# Macropad_schem_1.net
KiCad netlist of a schematic drawn in EAGLE
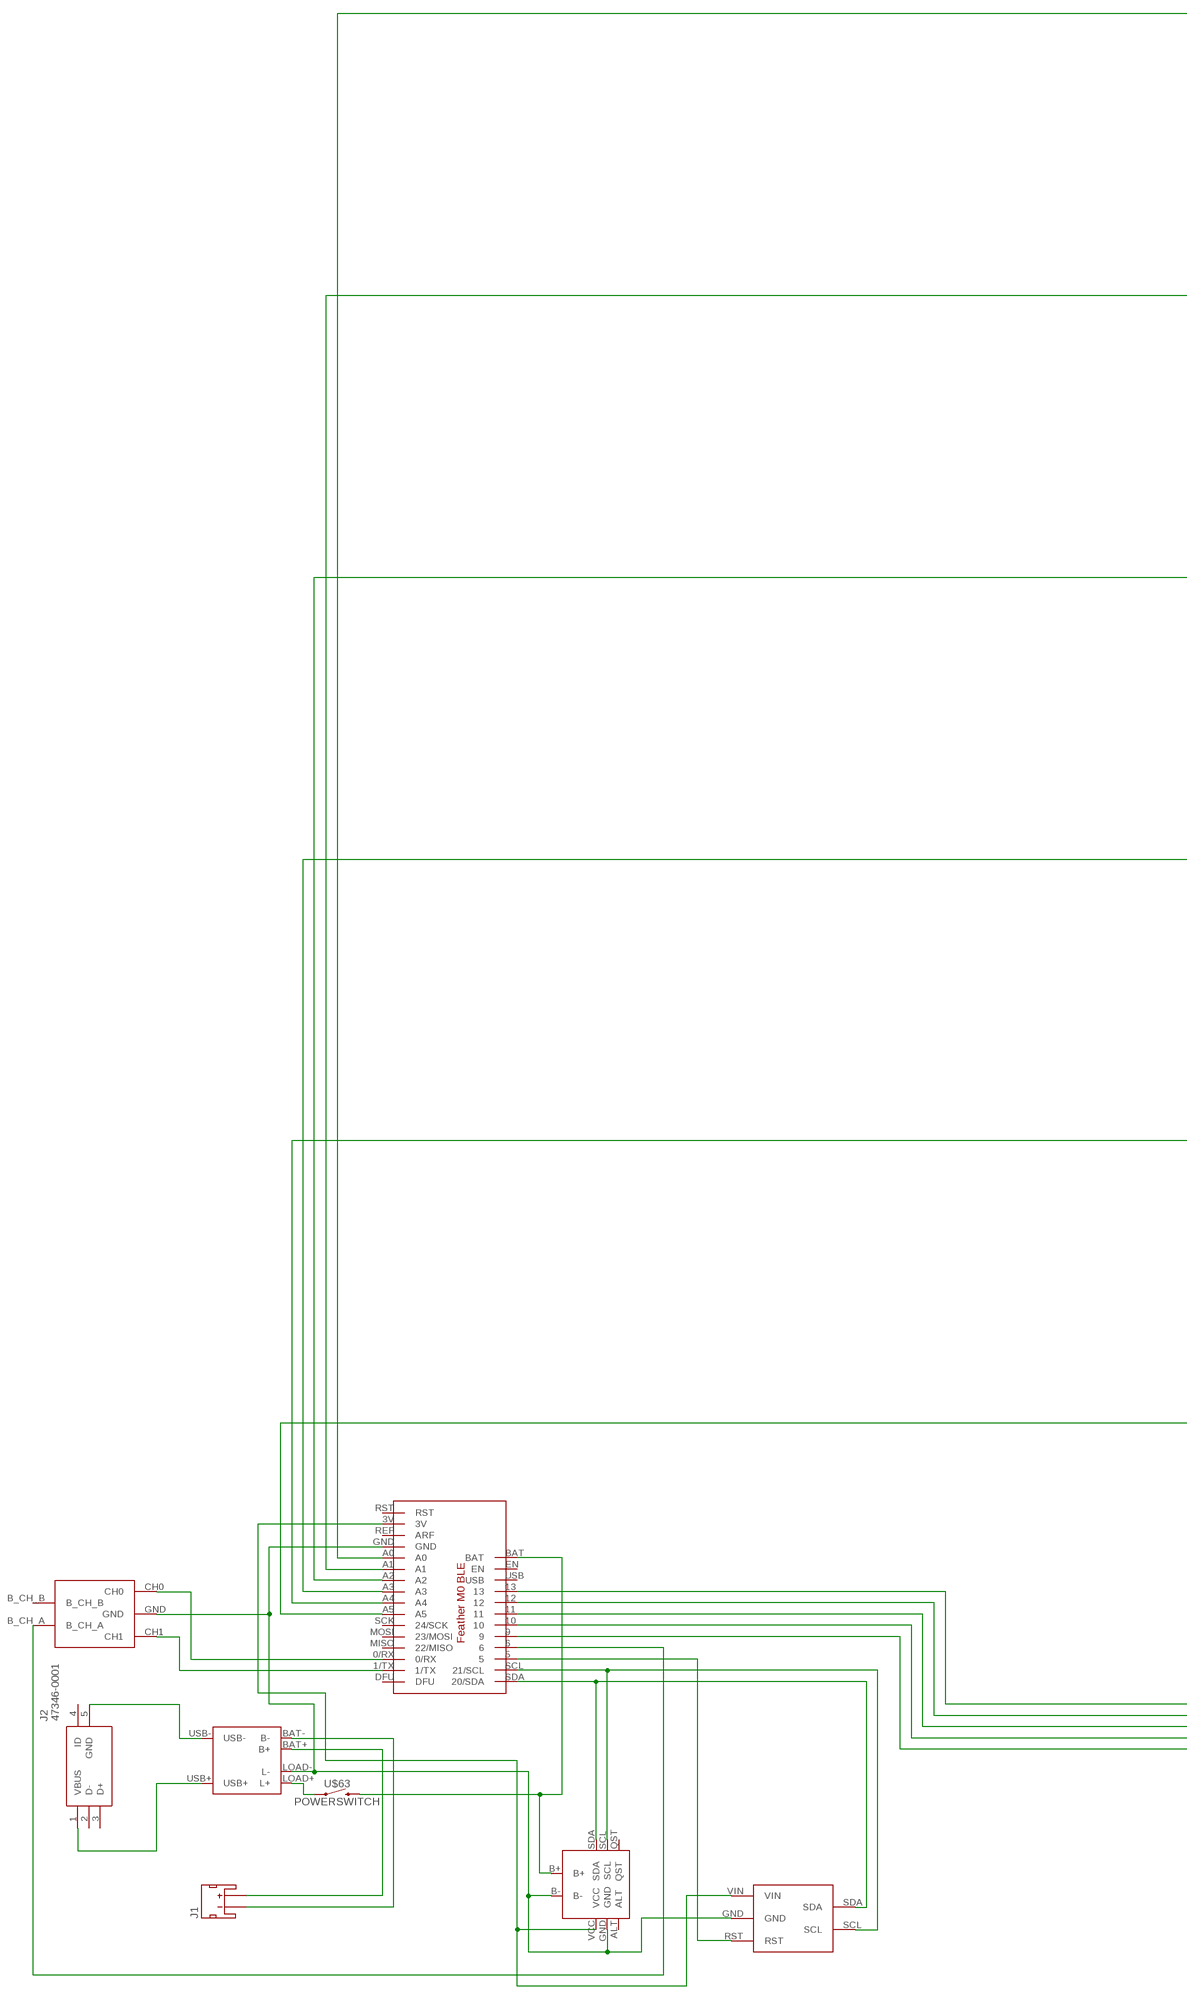
[diagram p0: schematic, sheet 1, part 1 of 2]
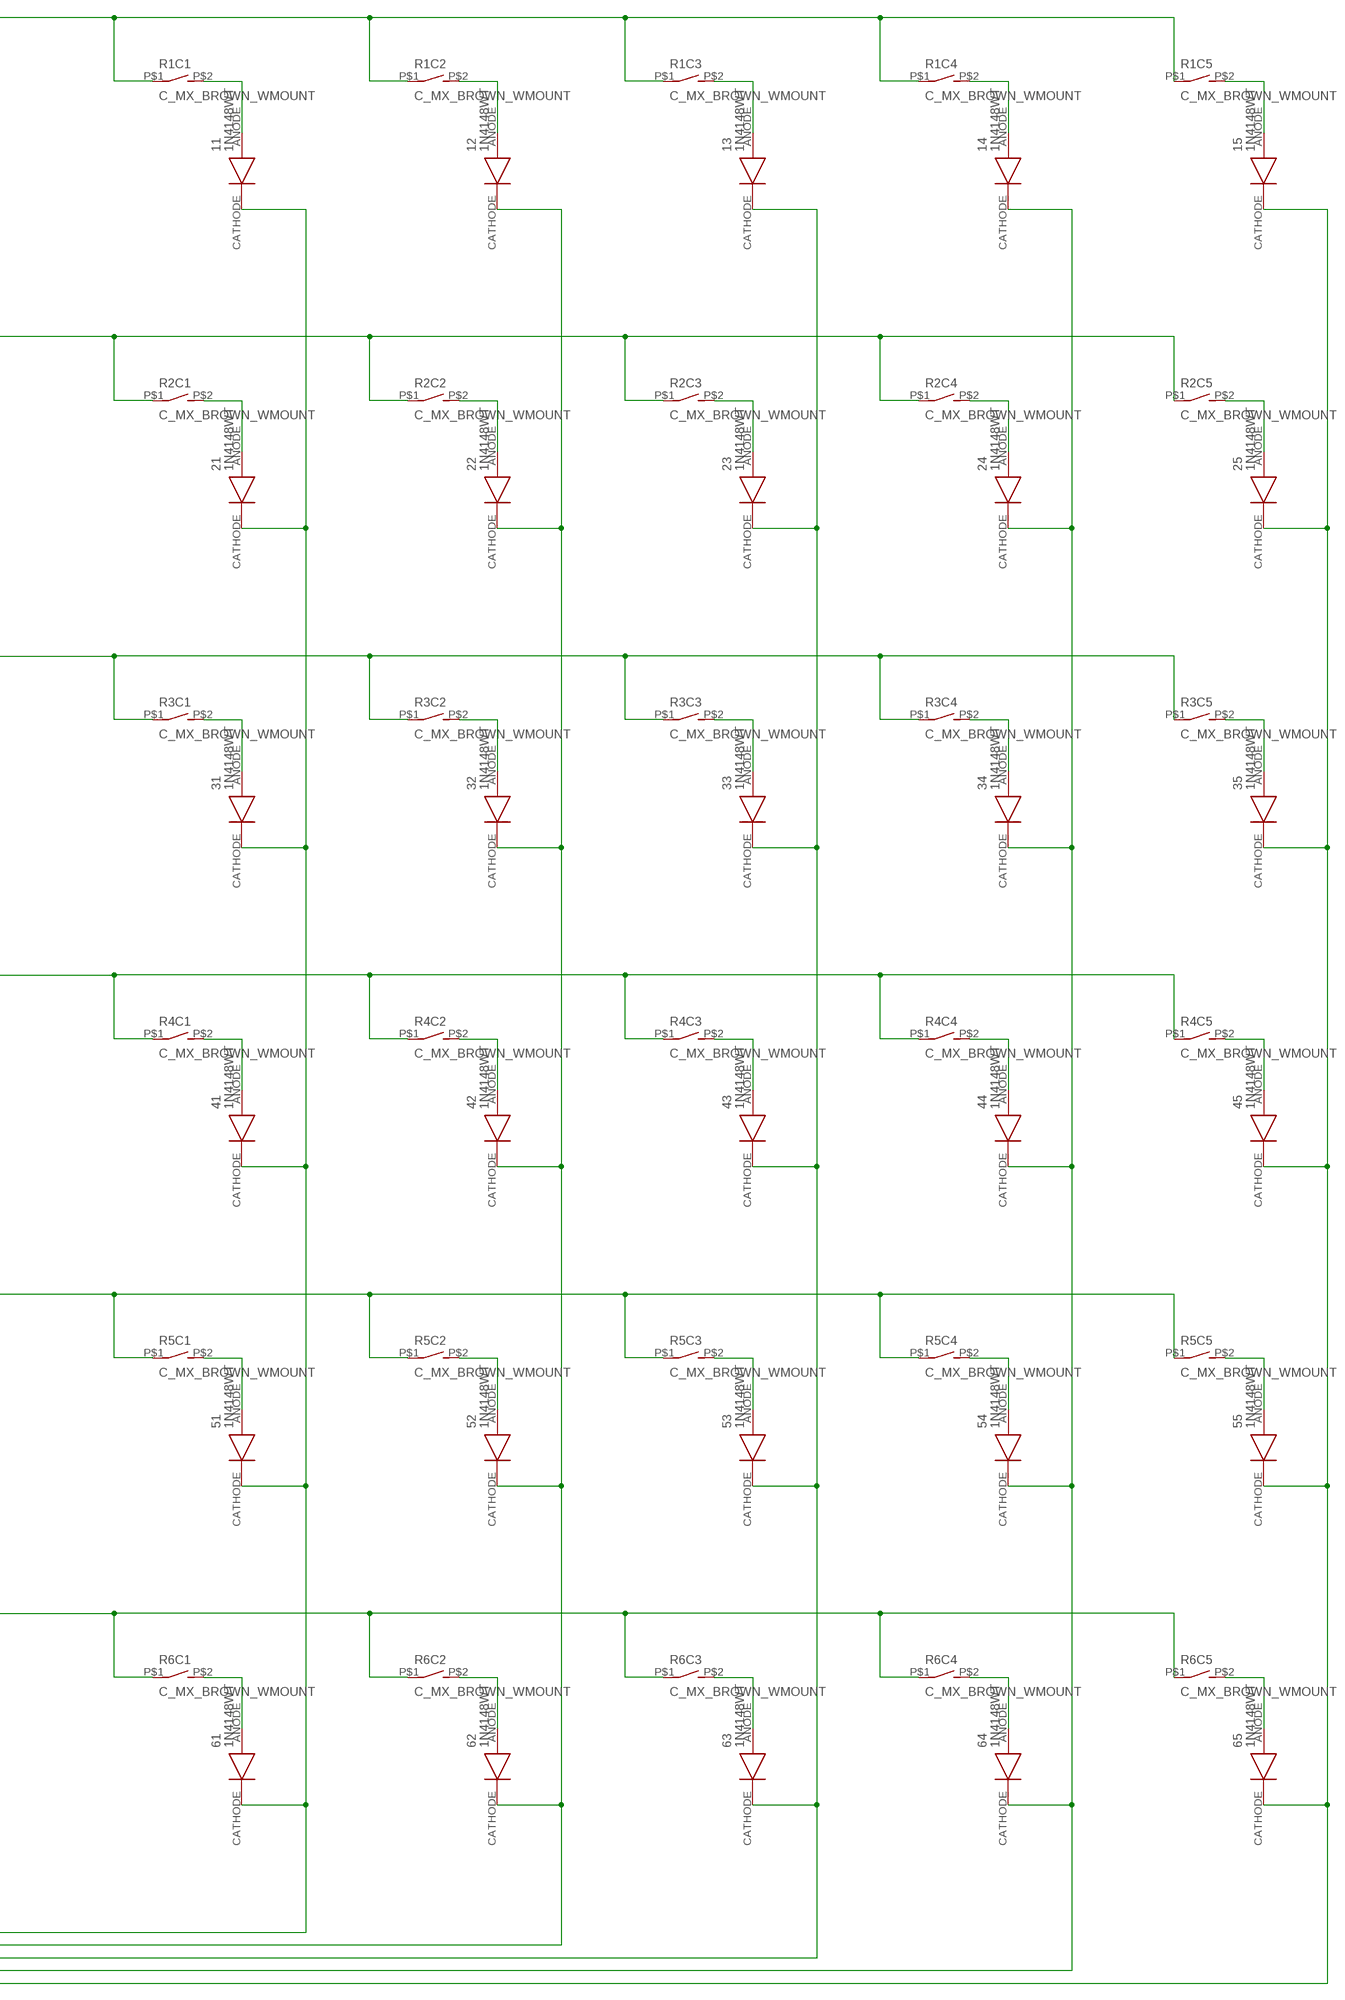
[diagram p1: schematic, sheet 1, part 2 of 2]

(export (version "E")
  (design (tool "Eeschema 10.0.6"))
  (components
    (comp (ref "11")
      (value "1N4148WT")
      (footprint "eagle-import:1N4148WT")
      (libsource (lib "eagle-import") (part "1N4148WT"))
    )
    (comp (ref "12")
      (value "1N4148WT")
      (footprint "eagle-import:1N4148WT")
      (libsource (lib "eagle-import") (part "1N4148WT"))
    )
    (comp (ref "13")
      (value "1N4148WT")
      (footprint "eagle-import:1N4148WT")
      (libsource (lib "eagle-import") (part "1N4148WT"))
    )
    (comp (ref "14")
      (value "1N4148WT")
      (footprint "eagle-import:1N4148WT")
      (libsource (lib "eagle-import") (part "1N4148WT"))
    )
    (comp (ref "15")
      (value "1N4148WT")
      (footprint "eagle-import:1N4148WT")
      (libsource (lib "eagle-import") (part "1N4148WT"))
    )
    (comp (ref "21")
      (value "1N4148WT")
      (footprint "eagle-import:1N4148WT")
      (libsource (lib "eagle-import") (part "1N4148WT"))
    )
    (comp (ref "22")
      (value "1N4148WT")
      (footprint "eagle-import:1N4148WT")
      (libsource (lib "eagle-import") (part "1N4148WT"))
    )
    (comp (ref "23")
      (value "1N4148WT")
      (footprint "eagle-import:1N4148WT")
      (libsource (lib "eagle-import") (part "1N4148WT"))
    )
    (comp (ref "24")
      (value "1N4148WT")
      (footprint "eagle-import:1N4148WT")
      (libsource (lib "eagle-import") (part "1N4148WT"))
    )
    (comp (ref "25")
      (value "1N4148WT")
      (footprint "eagle-import:1N4148WT")
      (libsource (lib "eagle-import") (part "1N4148WT"))
    )
    (comp (ref "31")
      (value "1N4148WT")
      (footprint "eagle-import:1N4148WT")
      (libsource (lib "eagle-import") (part "1N4148WT"))
    )
    (comp (ref "32")
      (value "1N4148WT")
      (footprint "eagle-import:1N4148WT")
      (libsource (lib "eagle-import") (part "1N4148WT"))
    )
    (comp (ref "33")
      (value "1N4148WT")
      (footprint "eagle-import:1N4148WT")
      (libsource (lib "eagle-import") (part "1N4148WT"))
    )
    (comp (ref "34")
      (value "1N4148WT")
      (footprint "eagle-import:1N4148WT")
      (libsource (lib "eagle-import") (part "1N4148WT"))
    )
    (comp (ref "35")
      (value "1N4148WT")
      (footprint "eagle-import:1N4148WT")
      (libsource (lib "eagle-import") (part "1N4148WT"))
    )
    (comp (ref "41")
      (value "1N4148WT")
      (footprint "eagle-import:1N4148WT")
      (libsource (lib "eagle-import") (part "1N4148WT"))
    )
    (comp (ref "42")
      (value "1N4148WT")
      (footprint "eagle-import:1N4148WT")
      (libsource (lib "eagle-import") (part "1N4148WT"))
    )
    (comp (ref "43")
      (value "1N4148WT")
      (footprint "eagle-import:1N4148WT")
      (libsource (lib "eagle-import") (part "1N4148WT"))
    )
    (comp (ref "44")
      (value "1N4148WT")
      (footprint "eagle-import:1N4148WT")
      (libsource (lib "eagle-import") (part "1N4148WT"))
    )
    (comp (ref "45")
      (value "1N4148WT")
      (footprint "eagle-import:1N4148WT")
      (libsource (lib "eagle-import") (part "1N4148WT"))
    )
    (comp (ref "51")
      (value "1N4148WT")
      (footprint "eagle-import:1N4148WT")
      (libsource (lib "eagle-import") (part "1N4148WT"))
    )
    (comp (ref "52")
      (value "1N4148WT")
      (footprint "eagle-import:1N4148WT")
      (libsource (lib "eagle-import") (part "1N4148WT"))
    )
    (comp (ref "53")
      (value "1N4148WT")
      (footprint "eagle-import:1N4148WT")
      (libsource (lib "eagle-import") (part "1N4148WT"))
    )
    (comp (ref "54")
      (value "1N4148WT")
      (footprint "eagle-import:1N4148WT")
      (libsource (lib "eagle-import") (part "1N4148WT"))
    )
    (comp (ref "55")
      (value "1N4148WT")
      (footprint "eagle-import:1N4148WT")
      (libsource (lib "eagle-import") (part "1N4148WT"))
    )
    (comp (ref "61")
      (value "1N4148WT")
      (footprint "eagle-import:1N4148WT")
      (libsource (lib "eagle-import") (part "1N4148WT"))
    )
    (comp (ref "62")
      (value "1N4148WT")
      (footprint "eagle-import:1N4148WT")
      (libsource (lib "eagle-import") (part "1N4148WT"))
    )
    (comp (ref "63")
      (value "1N4148WT")
      (footprint "eagle-import:1N4148WT")
      (libsource (lib "eagle-import") (part "1N4148WT"))
    )
    (comp (ref "64")
      (value "1N4148WT")
      (footprint "eagle-import:1N4148WT")
      (libsource (lib "eagle-import") (part "1N4148WT"))
    )
    (comp (ref "65")
      (value "1N4148WT")
      (footprint "eagle-import:1N4148WT")
      (libsource (lib "eagle-import") (part "1N4148WT"))
    )
    (comp (ref "J1")
      (value "JST_2MM_MALE")
      (footprint "eagle-import:JST-2-SMD")
      (libsource (lib "eagle-import") (part "JST_2MM_MALE"))
    )
    (comp (ref "J2")
      (value "47346-0001")
      (footprint "eagle-import:47346-0001")
      (fields (field (name "MOUSER_PART_NUMBER") "538-47346-0001"))
      (libsource (lib "eagle-import") (part "47346-0001"))
    )
    (comp (ref "R1C1")
      (value "C_MX_BROWN_WMOUNT")
      (footprint "eagle-import:C_MX_BROWN_WMOUNT")
      (libsource (lib "eagle-import") (part "C_MX_BROWN_WMOUNT"))
    )
    (comp (ref "R1C2")
      (value "C_MX_BROWN_WMOUNT")
      (footprint "eagle-import:C_MX_BROWN_WMOUNT")
      (libsource (lib "eagle-import") (part "C_MX_BROWN_WMOUNT"))
    )
    (comp (ref "R1C3")
      (value "C_MX_BROWN_WMOUNT")
      (footprint "eagle-import:C_MX_BROWN_WMOUNT")
      (libsource (lib "eagle-import") (part "C_MX_BROWN_WMOUNT"))
    )
    (comp (ref "R1C4")
      (value "C_MX_BROWN_WMOUNT")
      (footprint "eagle-import:C_MX_BROWN_WMOUNT")
      (libsource (lib "eagle-import") (part "C_MX_BROWN_WMOUNT"))
    )
    (comp (ref "R1C5")
      (value "C_MX_BROWN_WMOUNT")
      (footprint "eagle-import:C_MX_BROWN_WMOUNT")
      (libsource (lib "eagle-import") (part "C_MX_BROWN_WMOUNT"))
    )
    (comp (ref "R2C1")
      (value "C_MX_BROWN_WMOUNT")
      (footprint "eagle-import:C_MX_BROWN_WMOUNT")
      (libsource (lib "eagle-import") (part "C_MX_BROWN_WMOUNT"))
    )
    (comp (ref "R2C2")
      (value "C_MX_BROWN_WMOUNT")
      (footprint "eagle-import:C_MX_BROWN_WMOUNT")
      (libsource (lib "eagle-import") (part "C_MX_BROWN_WMOUNT"))
    )
    (comp (ref "R2C3")
      (value "C_MX_BROWN_WMOUNT")
      (footprint "eagle-import:C_MX_BROWN_WMOUNT")
      (libsource (lib "eagle-import") (part "C_MX_BROWN_WMOUNT"))
    )
    (comp (ref "R2C4")
      (value "C_MX_BROWN_WMOUNT")
      (footprint "eagle-import:C_MX_BROWN_WMOUNT")
      (libsource (lib "eagle-import") (part "C_MX_BROWN_WMOUNT"))
    )
    (comp (ref "R2C5")
      (value "C_MX_BROWN_WMOUNT")
      (footprint "eagle-import:C_MX_BROWN_WMOUNT")
      (libsource (lib "eagle-import") (part "C_MX_BROWN_WMOUNT"))
    )
    (comp (ref "R3C1")
      (value "C_MX_BROWN_WMOUNT")
      (footprint "eagle-import:C_MX_BROWN_WMOUNT")
      (libsource (lib "eagle-import") (part "C_MX_BROWN_WMOUNT"))
    )
    (comp (ref "R3C2")
      (value "C_MX_BROWN_WMOUNT")
      (footprint "eagle-import:C_MX_BROWN_WMOUNT")
      (libsource (lib "eagle-import") (part "C_MX_BROWN_WMOUNT"))
    )
    (comp (ref "R3C3")
      (value "C_MX_BROWN_WMOUNT")
      (footprint "eagle-import:C_MX_BROWN_WMOUNT")
      (libsource (lib "eagle-import") (part "C_MX_BROWN_WMOUNT"))
    )
    (comp (ref "R3C4")
      (value "C_MX_BROWN_WMOUNT")
      (footprint "eagle-import:C_MX_BROWN_WMOUNT")
      (libsource (lib "eagle-import") (part "C_MX_BROWN_WMOUNT"))
    )
    (comp (ref "R3C5")
      (value "C_MX_BROWN_WMOUNT")
      (footprint "eagle-import:C_MX_BROWN_WMOUNT")
      (libsource (lib "eagle-import") (part "C_MX_BROWN_WMOUNT"))
    )
    (comp (ref "R4C1")
      (value "C_MX_BROWN_WMOUNT")
      (footprint "eagle-import:C_MX_BROWN_WMOUNT")
      (libsource (lib "eagle-import") (part "C_MX_BROWN_WMOUNT"))
    )
    (comp (ref "R4C2")
      (value "C_MX_BROWN_WMOUNT")
      (footprint "eagle-import:C_MX_BROWN_WMOUNT")
      (libsource (lib "eagle-import") (part "C_MX_BROWN_WMOUNT"))
    )
    (comp (ref "R4C3")
      (value "C_MX_BROWN_WMOUNT")
      (footprint "eagle-import:C_MX_BROWN_WMOUNT")
      (libsource (lib "eagle-import") (part "C_MX_BROWN_WMOUNT"))
    )
    (comp (ref "R4C4")
      (value "C_MX_BROWN_WMOUNT")
      (footprint "eagle-import:C_MX_BROWN_WMOUNT")
      (libsource (lib "eagle-import") (part "C_MX_BROWN_WMOUNT"))
    )
    (comp (ref "R4C5")
      (value "C_MX_BROWN_WMOUNT")
      (footprint "eagle-import:C_MX_BROWN_WMOUNT")
      (libsource (lib "eagle-import") (part "C_MX_BROWN_WMOUNT"))
    )
    (comp (ref "R5C1")
      (value "C_MX_BROWN_WMOUNT")
      (footprint "eagle-import:C_MX_BROWN_WMOUNT")
      (libsource (lib "eagle-import") (part "C_MX_BROWN_WMOUNT"))
    )
    (comp (ref "R5C2")
      (value "C_MX_BROWN_WMOUNT")
      (footprint "eagle-import:C_MX_BROWN_WMOUNT")
      (libsource (lib "eagle-import") (part "C_MX_BROWN_WMOUNT"))
    )
    (comp (ref "R5C3")
      (value "C_MX_BROWN_WMOUNT")
      (footprint "eagle-import:C_MX_BROWN_WMOUNT")
      (libsource (lib "eagle-import") (part "C_MX_BROWN_WMOUNT"))
    )
    (comp (ref "R5C4")
      (value "C_MX_BROWN_WMOUNT")
      (footprint "eagle-import:C_MX_BROWN_WMOUNT")
      (libsource (lib "eagle-import") (part "C_MX_BROWN_WMOUNT"))
    )
    (comp (ref "R5C5")
      (value "C_MX_BROWN_WMOUNT")
      (footprint "eagle-import:C_MX_BROWN_WMOUNT")
      (libsource (lib "eagle-import") (part "C_MX_BROWN_WMOUNT"))
    )
    (comp (ref "R6C1")
      (value "C_MX_BROWN_WMOUNT")
      (footprint "eagle-import:C_MX_BROWN_WMOUNT")
      (libsource (lib "eagle-import") (part "C_MX_BROWN_WMOUNT"))
    )
    (comp (ref "R6C2")
      (value "C_MX_BROWN_WMOUNT")
      (footprint "eagle-import:C_MX_BROWN_WMOUNT")
      (libsource (lib "eagle-import") (part "C_MX_BROWN_WMOUNT"))
    )
    (comp (ref "R6C3")
      (value "C_MX_BROWN_WMOUNT")
      (footprint "eagle-import:C_MX_BROWN_WMOUNT")
      (libsource (lib "eagle-import") (part "C_MX_BROWN_WMOUNT"))
    )
    (comp (ref "R6C4")
      (value "C_MX_BROWN_WMOUNT")
      (footprint "eagle-import:C_MX_BROWN_WMOUNT")
      (libsource (lib "eagle-import") (part "C_MX_BROWN_WMOUNT"))
    )
    (comp (ref "R6C5")
      (value "C_MX_BROWN_WMOUNT")
      (footprint "eagle-import:C_MX_BROWN_WMOUNT")
      (libsource (lib "eagle-import") (part "C_MX_BROWN_WMOUNT"))
    )
    (comp (ref "U$61")
      (value "ADA_FEATHER_M0_BLE")
      (footprint "eagle-import:ADA_FEATHER_M0_BLE")
      (libsource (lib "eagle-import") (part "ADA_FEATHER_M0_BLE"))
    )
    (comp (ref "U$62")
      (value "ADA_LIIONCHARGER_V1.2")
      (footprint "eagle-import:ADA_LIIONCHARGER_V1.2")
      (libsource (lib "eagle-import") (part "ADA_LIIONCHARGER_V1.2"))
    )
    (comp (ref "U$63")
      (value "POWERSWITCH")
      (footprint "eagle-import:POWERSWITCH")
      (libsource (lib "eagle-import") (part "POWERSWITCH"))
    )
    (comp (ref "U$64")
      (value "LIPO_FUEL_GAUGE")
      (footprint "eagle-import:LIPO_FUEL_GAUGE")
      (libsource (lib "eagle-import") (part "LIPO_FUEL_GAUGE"))
    )
    (comp (ref "U$65")
      (value "COM-09117")
      (footprint "eagle-import:COM-09117")
      (libsource (lib "eagle-import") (part "COM-09117"))
    )
    (comp (ref "U$66")
      (value "I2C_OLED_DISP")
      (footprint "eagle-import:I2C_OLED_DISP")
      (libsource (lib "eagle-import") (part "I2C_OLED_DISP"))
    )
  )
  (nets
    (net (code "1") (name "Net-(11-PadCATHODE)") (class "Default")
      (node (ref "11") (pin "CATHODE") (pinfunction "CATHODE_CATHODE") (pintype "bidirectional"))
      (node (ref "21") (pin "CATHODE") (pinfunction "CATHODE_CATHODE") (pintype "bidirectional"))
      (node (ref "31") (pin "CATHODE") (pinfunction "CATHODE_CATHODE") (pintype "bidirectional"))
      (node (ref "41") (pin "CATHODE") (pinfunction "CATHODE_CATHODE") (pintype "bidirectional"))
      (node (ref "51") (pin "CATHODE") (pinfunction "CATHODE_CATHODE") (pintype "bidirectional"))
      (node (ref "61") (pin "CATHODE") (pinfunction "CATHODE_CATHODE") (pintype "bidirectional"))
      (node (ref "U$61") (pin "13") (pinfunction "13_13") (pintype "bidirectional"))
    )
    (net (code "2") (name "Net-(12-PadCATHODE)") (class "Default")
      (node (ref "12") (pin "CATHODE") (pinfunction "CATHODE_CATHODE") (pintype "bidirectional"))
      (node (ref "22") (pin "CATHODE") (pinfunction "CATHODE_CATHODE") (pintype "bidirectional"))
      (node (ref "32") (pin "CATHODE") (pinfunction "CATHODE_CATHODE") (pintype "bidirectional"))
      (node (ref "42") (pin "CATHODE") (pinfunction "CATHODE_CATHODE") (pintype "bidirectional"))
      (node (ref "52") (pin "CATHODE") (pinfunction "CATHODE_CATHODE") (pintype "bidirectional"))
      (node (ref "62") (pin "CATHODE") (pinfunction "CATHODE_CATHODE") (pintype "bidirectional"))
      (node (ref "U$61") (pin "12") (pinfunction "12_12") (pintype "bidirectional"))
    )
    (net (code "3") (name "Net-(13-PadCATHODE)") (class "Default")
      (node (ref "13") (pin "CATHODE") (pinfunction "CATHODE_CATHODE") (pintype "bidirectional"))
      (node (ref "23") (pin "CATHODE") (pinfunction "CATHODE_CATHODE") (pintype "bidirectional"))
      (node (ref "33") (pin "CATHODE") (pinfunction "CATHODE_CATHODE") (pintype "bidirectional"))
      (node (ref "43") (pin "CATHODE") (pinfunction "CATHODE_CATHODE") (pintype "bidirectional"))
      (node (ref "53") (pin "CATHODE") (pinfunction "CATHODE_CATHODE") (pintype "bidirectional"))
      (node (ref "63") (pin "CATHODE") (pinfunction "CATHODE_CATHODE") (pintype "bidirectional"))
      (node (ref "U$61") (pin "11") (pinfunction "11_11") (pintype "bidirectional"))
    )
    (net (code "4") (name "Net-(14-PadCATHODE)") (class "Default")
      (node (ref "14") (pin "CATHODE") (pinfunction "CATHODE_CATHODE") (pintype "bidirectional"))
      (node (ref "24") (pin "CATHODE") (pinfunction "CATHODE_CATHODE") (pintype "bidirectional"))
      (node (ref "34") (pin "CATHODE") (pinfunction "CATHODE_CATHODE") (pintype "bidirectional"))
      (node (ref "44") (pin "CATHODE") (pinfunction "CATHODE_CATHODE") (pintype "bidirectional"))
      (node (ref "54") (pin "CATHODE") (pinfunction "CATHODE_CATHODE") (pintype "bidirectional"))
      (node (ref "64") (pin "CATHODE") (pinfunction "CATHODE_CATHODE") (pintype "bidirectional"))
      (node (ref "U$61") (pin "10") (pinfunction "10_10") (pintype "bidirectional"))
    )
    (net (code "5") (name "Net-(15-PadCATHODE)") (class "Default")
      (node (ref "15") (pin "CATHODE") (pinfunction "CATHODE_CATHODE") (pintype "bidirectional"))
      (node (ref "25") (pin "CATHODE") (pinfunction "CATHODE_CATHODE") (pintype "bidirectional"))
      (node (ref "35") (pin "CATHODE") (pinfunction "CATHODE_CATHODE") (pintype "bidirectional"))
      (node (ref "45") (pin "CATHODE") (pinfunction "CATHODE_CATHODE") (pintype "bidirectional"))
      (node (ref "55") (pin "CATHODE") (pinfunction "CATHODE_CATHODE") (pintype "bidirectional"))
      (node (ref "65") (pin "CATHODE") (pinfunction "CATHODE_CATHODE") (pintype "bidirectional"))
      (node (ref "U$61") (pin "9") (pinfunction "9_9") (pintype "bidirectional"))
    )
    (net (code "6") (name "Net-(J1-+)") (class "Default")
      (node (ref "J1") (pin "2") (pinfunction "+_2") (pintype "bidirectional"))
      (node (ref "U$62") (pin "BAT+") (pinfunction "B+_BAT+") (pintype "bidirectional"))
    )
    (net (code "7") (name "Net-(J1--)") (class "Default")
      (node (ref "J1") (pin "1") (pinfunction "-_1") (pintype "bidirectional"))
      (node (ref "U$62") (pin "BAT-") (pinfunction "B-_BAT-") (pintype "bidirectional"))
    )
    (net (code "8") (name "Net-(J2-GND)") (class "Default")
      (node (ref "J2") (pin "5") (pinfunction "GND_5") (pintype "bidirectional"))
      (node (ref "U$62") (pin "USB-") (pinfunction "USB-_USB-") (pintype "bidirectional"))
    )
    (net (code "9") (name "Net-(J2-VBUS)") (class "Default")
      (node (ref "J2") (pin "1") (pinfunction "VBUS_1") (pintype "bidirectional"))
      (node (ref "U$62") (pin "USB+") (pinfunction "USB+_USB+") (pintype "bidirectional"))
    )
    (net (code "10") (name "Net-(R1C1-1)") (class "Default")
      (node (ref "R1C1") (pin "P$1") (pinfunction "1_P$1") (pintype "passive"))
      (node (ref "R1C2") (pin "P$1") (pinfunction "1_P$1") (pintype "passive"))
      (node (ref "R1C3") (pin "P$1") (pinfunction "1_P$1") (pintype "passive"))
      (node (ref "R1C4") (pin "P$1") (pinfunction "1_P$1") (pintype "passive"))
      (node (ref "R1C5") (pin "P$1") (pinfunction "1_P$1") (pintype "passive"))
      (node (ref "U$61") (pin "A0") (pinfunction "A0_A0") (pintype "bidirectional"))
    )
    (net (code "11") (name "Net-(R1C1-2)") (class "Default")
      (node (ref "11") (pin "ANODE") (pinfunction "ANODE_ANODE") (pintype "bidirectional"))
      (node (ref "R1C1") (pin "P$2") (pinfunction "2_P$2") (pintype "passive"))
    )
    (net (code "12") (name "Net-(R1C2-2)") (class "Default")
      (node (ref "12") (pin "ANODE") (pinfunction "ANODE_ANODE") (pintype "bidirectional"))
      (node (ref "R1C2") (pin "P$2") (pinfunction "2_P$2") (pintype "passive"))
    )
    (net (code "13") (name "Net-(R1C3-2)") (class "Default")
      (node (ref "13") (pin "ANODE") (pinfunction "ANODE_ANODE") (pintype "bidirectional"))
      (node (ref "R1C3") (pin "P$2") (pinfunction "2_P$2") (pintype "passive"))
    )
    (net (code "14") (name "Net-(R1C4-2)") (class "Default")
      (node (ref "14") (pin "ANODE") (pinfunction "ANODE_ANODE") (pintype "bidirectional"))
      (node (ref "R1C4") (pin "P$2") (pinfunction "2_P$2") (pintype "passive"))
    )
    (net (code "15") (name "Net-(R1C5-2)") (class "Default")
      (node (ref "15") (pin "ANODE") (pinfunction "ANODE_ANODE") (pintype "bidirectional"))
      (node (ref "R1C5") (pin "P$2") (pinfunction "2_P$2") (pintype "passive"))
    )
    (net (code "16") (name "Net-(R2C1-1)") (class "Default")
      (node (ref "R2C1") (pin "P$1") (pinfunction "1_P$1") (pintype "passive"))
      (node (ref "R2C2") (pin "P$1") (pinfunction "1_P$1") (pintype "passive"))
      (node (ref "R2C3") (pin "P$1") (pinfunction "1_P$1") (pintype "passive"))
      (node (ref "R2C4") (pin "P$1") (pinfunction "1_P$1") (pintype "passive"))
      (node (ref "R2C5") (pin "P$1") (pinfunction "1_P$1") (pintype "passive"))
      (node (ref "U$61") (pin "A1") (pinfunction "A1_A1") (pintype "bidirectional"))
    )
    (net (code "17") (name "Net-(R2C1-2)") (class "Default")
      (node (ref "21") (pin "ANODE") (pinfunction "ANODE_ANODE") (pintype "bidirectional"))
      (node (ref "R2C1") (pin "P$2") (pinfunction "2_P$2") (pintype "passive"))
    )
    (net (code "18") (name "Net-(R2C2-2)") (class "Default")
      (node (ref "22") (pin "ANODE") (pinfunction "ANODE_ANODE") (pintype "bidirectional"))
      (node (ref "R2C2") (pin "P$2") (pinfunction "2_P$2") (pintype "passive"))
    )
    (net (code "19") (name "Net-(R2C3-2)") (class "Default")
      (node (ref "23") (pin "ANODE") (pinfunction "ANODE_ANODE") (pintype "bidirectional"))
      (node (ref "R2C3") (pin "P$2") (pinfunction "2_P$2") (pintype "passive"))
    )
    (net (code "20") (name "Net-(R2C4-2)") (class "Default")
      (node (ref "24") (pin "ANODE") (pinfunction "ANODE_ANODE") (pintype "bidirectional"))
      (node (ref "R2C4") (pin "P$2") (pinfunction "2_P$2") (pintype "passive"))
    )
    (net (code "21") (name "Net-(R2C5-2)") (class "Default")
      (node (ref "25") (pin "ANODE") (pinfunction "ANODE_ANODE") (pintype "bidirectional"))
      (node (ref "R2C5") (pin "P$2") (pinfunction "2_P$2") (pintype "passive"))
    )
    (net (code "22") (name "Net-(R3C1-1)") (class "Default")
      (node (ref "R3C1") (pin "P$1") (pinfunction "1_P$1") (pintype "passive"))
      (node (ref "R3C2") (pin "P$1") (pinfunction "1_P$1") (pintype "passive"))
      (node (ref "R3C3") (pin "P$1") (pinfunction "1_P$1") (pintype "passive"))
      (node (ref "R3C4") (pin "P$1") (pinfunction "1_P$1") (pintype "passive"))
      (node (ref "R3C5") (pin "P$1") (pinfunction "1_P$1") (pintype "passive"))
      (node (ref "U$61") (pin "A2") (pinfunction "A2_A2") (pintype "bidirectional"))
    )
    (net (code "23") (name "Net-(R3C1-2)") (class "Default")
      (node (ref "31") (pin "ANODE") (pinfunction "ANODE_ANODE") (pintype "bidirectional"))
      (node (ref "R3C1") (pin "P$2") (pinfunction "2_P$2") (pintype "passive"))
    )
    (net (code "24") (name "Net-(R3C2-2)") (class "Default")
      (node (ref "32") (pin "ANODE") (pinfunction "ANODE_ANODE") (pintype "bidirectional"))
      (node (ref "R3C2") (pin "P$2") (pinfunction "2_P$2") (pintype "passive"))
    )
    (net (code "25") (name "Net-(R3C3-2)") (class "Default")
      (node (ref "33") (pin "ANODE") (pinfunction "ANODE_ANODE") (pintype "bidirectional"))
      (node (ref "R3C3") (pin "P$2") (pinfunction "2_P$2") (pintype "passive"))
    )
    (net (code "26") (name "Net-(R3C4-2)") (class "Default")
      (node (ref "34") (pin "ANODE") (pinfunction "ANODE_ANODE") (pintype "bidirectional"))
      (node (ref "R3C4") (pin "P$2") (pinfunction "2_P$2") (pintype "passive"))
    )
    (net (code "27") (name "Net-(R3C5-2)") (class "Default")
      (node (ref "35") (pin "ANODE") (pinfunction "ANODE_ANODE") (pintype "bidirectional"))
      (node (ref "R3C5") (pin "P$2") (pinfunction "2_P$2") (pintype "passive"))
    )
    (net (code "28") (name "Net-(R4C1-1)") (class "Default")
      (node (ref "R4C1") (pin "P$1") (pinfunction "1_P$1") (pintype "passive"))
      (node (ref "R4C2") (pin "P$1") (pinfunction "1_P$1") (pintype "passive"))
      (node (ref "R4C3") (pin "P$1") (pinfunction "1_P$1") (pintype "passive"))
      (node (ref "R4C4") (pin "P$1") (pinfunction "1_P$1") (pintype "passive"))
      (node (ref "R4C5") (pin "P$1") (pinfunction "1_P$1") (pintype "passive"))
      (node (ref "U$61") (pin "A3") (pinfunction "A3_A3") (pintype "bidirectional"))
    )
    (net (code "29") (name "Net-(R4C1-2)") (class "Default")
      (node (ref "41") (pin "ANODE") (pinfunction "ANODE_ANODE") (pintype "bidirectional"))
      (node (ref "R4C1") (pin "P$2") (pinfunction "2_P$2") (pintype "passive"))
    )
    (net (code "30") (name "Net-(R4C2-2)") (class "Default")
      (node (ref "42") (pin "ANODE") (pinfunction "ANODE_ANODE") (pintype "bidirectional"))
      (node (ref "R4C2") (pin "P$2") (pinfunction "2_P$2") (pintype "passive"))
    )
    (net (code "31") (name "Net-(R4C3-2)") (class "Default")
      (node (ref "43") (pin "ANODE") (pinfunction "ANODE_ANODE") (pintype "bidirectional"))
      (node (ref "R4C3") (pin "P$2") (pinfunction "2_P$2") (pintype "passive"))
    )
    (net (code "32") (name "Net-(R4C4-2)") (class "Default")
      (node (ref "44") (pin "ANODE") (pinfunction "ANODE_ANODE") (pintype "bidirectional"))
      (node (ref "R4C4") (pin "P$2") (pinfunction "2_P$2") (pintype "passive"))
    )
    (net (code "33") (name "Net-(R4C5-2)") (class "Default")
      (node (ref "45") (pin "ANODE") (pinfunction "ANODE_ANODE") (pintype "bidirectional"))
      (node (ref "R4C5") (pin "P$2") (pinfunction "2_P$2") (pintype "passive"))
    )
    (net (code "34") (name "Net-(R5C1-1)") (class "Default")
      (node (ref "R5C1") (pin "P$1") (pinfunction "1_P$1") (pintype "passive"))
      (node (ref "R5C2") (pin "P$1") (pinfunction "1_P$1") (pintype "passive"))
      (node (ref "R5C3") (pin "P$1") (pinfunction "1_P$1") (pintype "passive"))
      (node (ref "R5C4") (pin "P$1") (pinfunction "1_P$1") (pintype "passive"))
      (node (ref "R5C5") (pin "P$1") (pinfunction "1_P$1") (pintype "passive"))
      (node (ref "U$61") (pin "A4") (pinfunction "A4_A4") (pintype "bidirectional"))
    )
    (net (code "35") (name "Net-(R5C1-2)") (class "Default")
      (node (ref "51") (pin "ANODE") (pinfunction "ANODE_ANODE") (pintype "bidirectional"))
      (node (ref "R5C1") (pin "P$2") (pinfunction "2_P$2") (pintype "passive"))
    )
    (net (code "36") (name "Net-(R5C2-2)") (class "Default")
      (node (ref "52") (pin "ANODE") (pinfunction "ANODE_ANODE") (pintype "bidirectional"))
      (node (ref "R5C2") (pin "P$2") (pinfunction "2_P$2") (pintype "passive"))
    )
    (net (code "37") (name "Net-(R5C3-2)") (class "Default")
      (node (ref "53") (pin "ANODE") (pinfunction "ANODE_ANODE") (pintype "bidirectional"))
      (node (ref "R5C3") (pin "P$2") (pinfunction "2_P$2") (pintype "passive"))
    )
    (net (code "38") (name "Net-(R5C4-2)") (class "Default")
      (node (ref "54") (pin "ANODE") (pinfunction "ANODE_ANODE") (pintype "bidirectional"))
      (node (ref "R5C4") (pin "P$2") (pinfunction "2_P$2") (pintype "passive"))
    )
    (net (code "39") (name "Net-(R5C5-2)") (class "Default")
      (node (ref "55") (pin "ANODE") (pinfunction "ANODE_ANODE") (pintype "bidirectional"))
      (node (ref "R5C5") (pin "P$2") (pinfunction "2_P$2") (pintype "passive"))
    )
    (net (code "40") (name "Net-(R6C1-1)") (class "Default")
      (node (ref "R6C1") (pin "P$1") (pinfunction "1_P$1") (pintype "passive"))
      (node (ref "R6C2") (pin "P$1") (pinfunction "1_P$1") (pintype "passive"))
      (node (ref "R6C3") (pin "P$1") (pinfunction "1_P$1") (pintype "passive"))
      (node (ref "R6C4") (pin "P$1") (pinfunction "1_P$1") (pintype "passive"))
      (node (ref "R6C5") (pin "P$1") (pinfunction "1_P$1") (pintype "passive"))
      (node (ref "U$61") (pin "A5") (pinfunction "A5_A5") (pintype "bidirectional"))
    )
    (net (code "41") (name "Net-(R6C1-2)") (class "Default")
      (node (ref "61") (pin "ANODE") (pinfunction "ANODE_ANODE") (pintype "bidirectional"))
      (node (ref "R6C1") (pin "P$2") (pinfunction "2_P$2") (pintype "passive"))
    )
    (net (code "42") (name "Net-(R6C2-2)") (class "Default")
      (node (ref "62") (pin "ANODE") (pinfunction "ANODE_ANODE") (pintype "bidirectional"))
      (node (ref "R6C2") (pin "P$2") (pinfunction "2_P$2") (pintype "passive"))
    )
    (net (code "43") (name "Net-(R6C3-2)") (class "Default")
      (node (ref "63") (pin "ANODE") (pinfunction "ANODE_ANODE") (pintype "bidirectional"))
      (node (ref "R6C3") (pin "P$2") (pinfunction "2_P$2") (pintype "passive"))
    )
    (net (code "44") (name "Net-(R6C4-2)") (class "Default")
      (node (ref "64") (pin "ANODE") (pinfunction "ANODE_ANODE") (pintype "bidirectional"))
      (node (ref "R6C4") (pin "P$2") (pinfunction "2_P$2") (pintype "passive"))
    )
    (net (code "45") (name "Net-(R6C5-2)") (class "Default")
      (node (ref "65") (pin "ANODE") (pinfunction "ANODE_ANODE") (pintype "bidirectional"))
      (node (ref "R6C5") (pin "P$2") (pinfunction "2_P$2") (pintype "passive"))
    )
    (net (code "46") (name "Net-(U$61-20{slash}SDA)") (class "Default")
      (node (ref "U$61") (pin "SDA") (pinfunction "20/SDA_SDA") (pintype "bidirectional"))
      (node (ref "U$64") (pin "SDA") (pinfunction "SDA_SDA") (pintype "bidirectional"))
      (node (ref "U$66") (pin "SDA") (pinfunction "SDA_SDA") (pintype "bidirectional"))
    )
    (net (code "47") (name "Net-(U$61-21{slash}SCL)") (class "Default")
      (node (ref "U$61") (pin "SCL") (pinfunction "21/SCL_SCL") (pintype "bidirectional"))
      (node (ref "U$64") (pin "SCL") (pinfunction "SCL_SCL") (pintype "bidirectional"))
      (node (ref "U$66") (pin "SCL") (pinfunction "SCL_SCL") (pintype "bidirectional"))
    )
    (net (code "48") (name "Net-(U$61-Pad0{slash}RX)") (class "Default")
      (node (ref "U$61") (pin "0/RX") (pinfunction "0/RX_0/RX") (pintype "bidirectional"))
      (node (ref "U$65") (pin "CH0") (pinfunction "CH0_CH0") (pintype "bidirectional"))
    )
    (net (code "49") (name "Net-(U$61-Pad1{slash}TX)") (class "Default")
      (node (ref "U$61") (pin "1/TX") (pinfunction "1/TX_1/TX") (pintype "bidirectional"))
      (node (ref "U$65") (pin "CH1") (pinfunction "CH1_CH1") (pintype "bidirectional"))
    )
    (net (code "50") (name "Net-(U$61-Pad3V)") (class "Default")
      (node (ref "U$61") (pin "3V") (pinfunction "3V_3V") (pintype "bidirectional"))
      (node (ref "U$64") (pin "VCC") (pinfunction "VCC_VCC") (pintype "bidirectional"))
      (node (ref "U$66") (pin "VIN") (pinfunction "VIN_VIN") (pintype "bidirectional"))
    )
    (net (code "51") (name "Net-(U$61-Pad5)") (class "Default")
      (node (ref "U$61") (pin "5") (pinfunction "5_5") (pintype "bidirectional"))
      (node (ref "U$66") (pin "RST") (pinfunction "RST_RST") (pintype "bidirectional"))
    )
    (net (code "52") (name "Net-(U$61-Pad6)") (class "Default")
      (node (ref "U$61") (pin "6") (pinfunction "6_6") (pintype "bidirectional"))
      (node (ref "U$65") (pin "B_CH_A") (pinfunction "B_CH_A_B_CH_A") (pintype "bidirectional"))
    )
    (net (code "53") (name "Net-(U$61-PadBAT)") (class "Default")
      (node (ref "U$61") (pin "BAT") (pinfunction "BAT_BAT") (pintype "bidirectional"))
      (node (ref "U$63") (pin "2") (pinfunction "2_2") (pintype "passive"))
      (node (ref "U$64") (pin "B+") (pinfunction "B+_B+") (pintype "bidirectional"))
    )
    (net (code "54") (name "Net-(U$62-L+)") (class "Default")
      (node (ref "U$62") (pin "LOAD+") (pinfunction "L+_LOAD+") (pintype "bidirectional"))
      (node (ref "U$63") (pin "1") (pinfunction "1_1") (pintype "passive"))
    )
    (net (code "55") (name "Net-(U$62-L-)") (class "Default")
      (node (ref "U$61") (pin "GND") (pinfunction "GND_GND") (pintype "bidirectional"))
      (node (ref "U$62") (pin "LOAD-") (pinfunction "L-_LOAD-") (pintype "bidirectional"))
      (node (ref "U$64") (pin "B-") (pinfunction "B-_B-") (pintype "bidirectional"))
      (node (ref "U$64") (pin "GND") (pinfunction "GND_GND") (pintype "bidirectional"))
      (node (ref "U$65") (pin "GND") (pinfunction "GND_GND") (pintype "bidirectional"))
      (node (ref "U$66") (pin "GND") (pinfunction "GND_GND") (pintype "bidirectional"))
    )
    (net (code "56") (name "unconnected-(J1-PAD1-PadNC1)") (class "Default")
      (node (ref "J1") (pin "NC1") (pinfunction "PAD1_NC1") (pintype "bidirectional"))
    )
    (net (code "57") (name "unconnected-(J1-PAD2-PadNC2)") (class "Default")
      (node (ref "J1") (pin "NC2") (pinfunction "PAD2_NC2") (pintype "bidirectional"))
    )
    (net (code "58") (name "unconnected-(J2-D+-Pad3)") (class "Default")
      (node (ref "J2") (pin "3") (pinfunction "D+_3") (pintype "bidirectional"))
    )
    (net (code "59") (name "unconnected-(J2-D--Pad2)") (class "Default")
      (node (ref "J2") (pin "2") (pinfunction "D-_2") (pintype "bidirectional"))
    )
    (net (code "60") (name "unconnected-(J2-ID-Pad4)") (class "Default")
      (node (ref "J2") (pin "4") (pinfunction "ID_4") (pintype "bidirectional"))
    )
    (net (code "61") (name "unconnected-(U$61-22{slash}MISO-PadMISO)") (class "Default")
      (node (ref "U$61") (pin "MISO") (pinfunction "22/MISO_MISO") (pintype "bidirectional"))
    )
    (net (code "62") (name "unconnected-(U$61-23{slash}MOSI-PadMOSI)") (class "Default")
      (node (ref "U$61") (pin "MOSI") (pinfunction "23/MOSI_MOSI") (pintype "bidirectional"))
    )
    (net (code "63") (name "unconnected-(U$61-24{slash}SCK-PadSCK)") (class "Default")
      (node (ref "U$61") (pin "SCK") (pinfunction "24/SCK_SCK") (pintype "bidirectional"))
    )
    (net (code "64") (name "unconnected-(U$61-ARF-PadREF)") (class "Default")
      (node (ref "U$61") (pin "REF") (pinfunction "ARF_REF") (pintype "bidirectional"))
    )
    (net (code "65") (name "unconnected-(U$61-PadDFU)") (class "Default")
      (node (ref "U$61") (pin "DFU") (pinfunction "DFU_DFU") (pintype "bidirectional"))
    )
    (net (code "66") (name "unconnected-(U$61-PadEN)") (class "Default")
      (node (ref "U$61") (pin "EN") (pinfunction "EN_EN") (pintype "bidirectional"))
    )
    (net (code "67") (name "unconnected-(U$61-PadRST)") (class "Default")
      (node (ref "U$61") (pin "RST") (pinfunction "RST_RST") (pintype "bidirectional"))
    )
    (net (code "68") (name "unconnected-(U$61-PadUSB)") (class "Default")
      (node (ref "U$61") (pin "USB") (pinfunction "USB_USB") (pintype "bidirectional"))
    )
    (net (code "69") (name "unconnected-(U$64-PadALT)") (class "Default")
      (node (ref "U$64") (pin "ALT") (pinfunction "ALT_ALT") (pintype "bidirectional"))
    )
    (net (code "70") (name "unconnected-(U$64-PadQST)") (class "Default")
      (node (ref "U$64") (pin "QST") (pinfunction "QST_QST") (pintype "bidirectional"))
    )
    (net (code "71") (name "unconnected-(U$65-PadB_CH_B)") (class "Default")
      (node (ref "U$65") (pin "B_CH_B") (pinfunction "B_CH_B_B_CH_B") (pintype "bidirectional"))
    )
  )
)
